# MCU_Power_Radio.net
KiCad netlist of a schematic drawn in Altium Designer
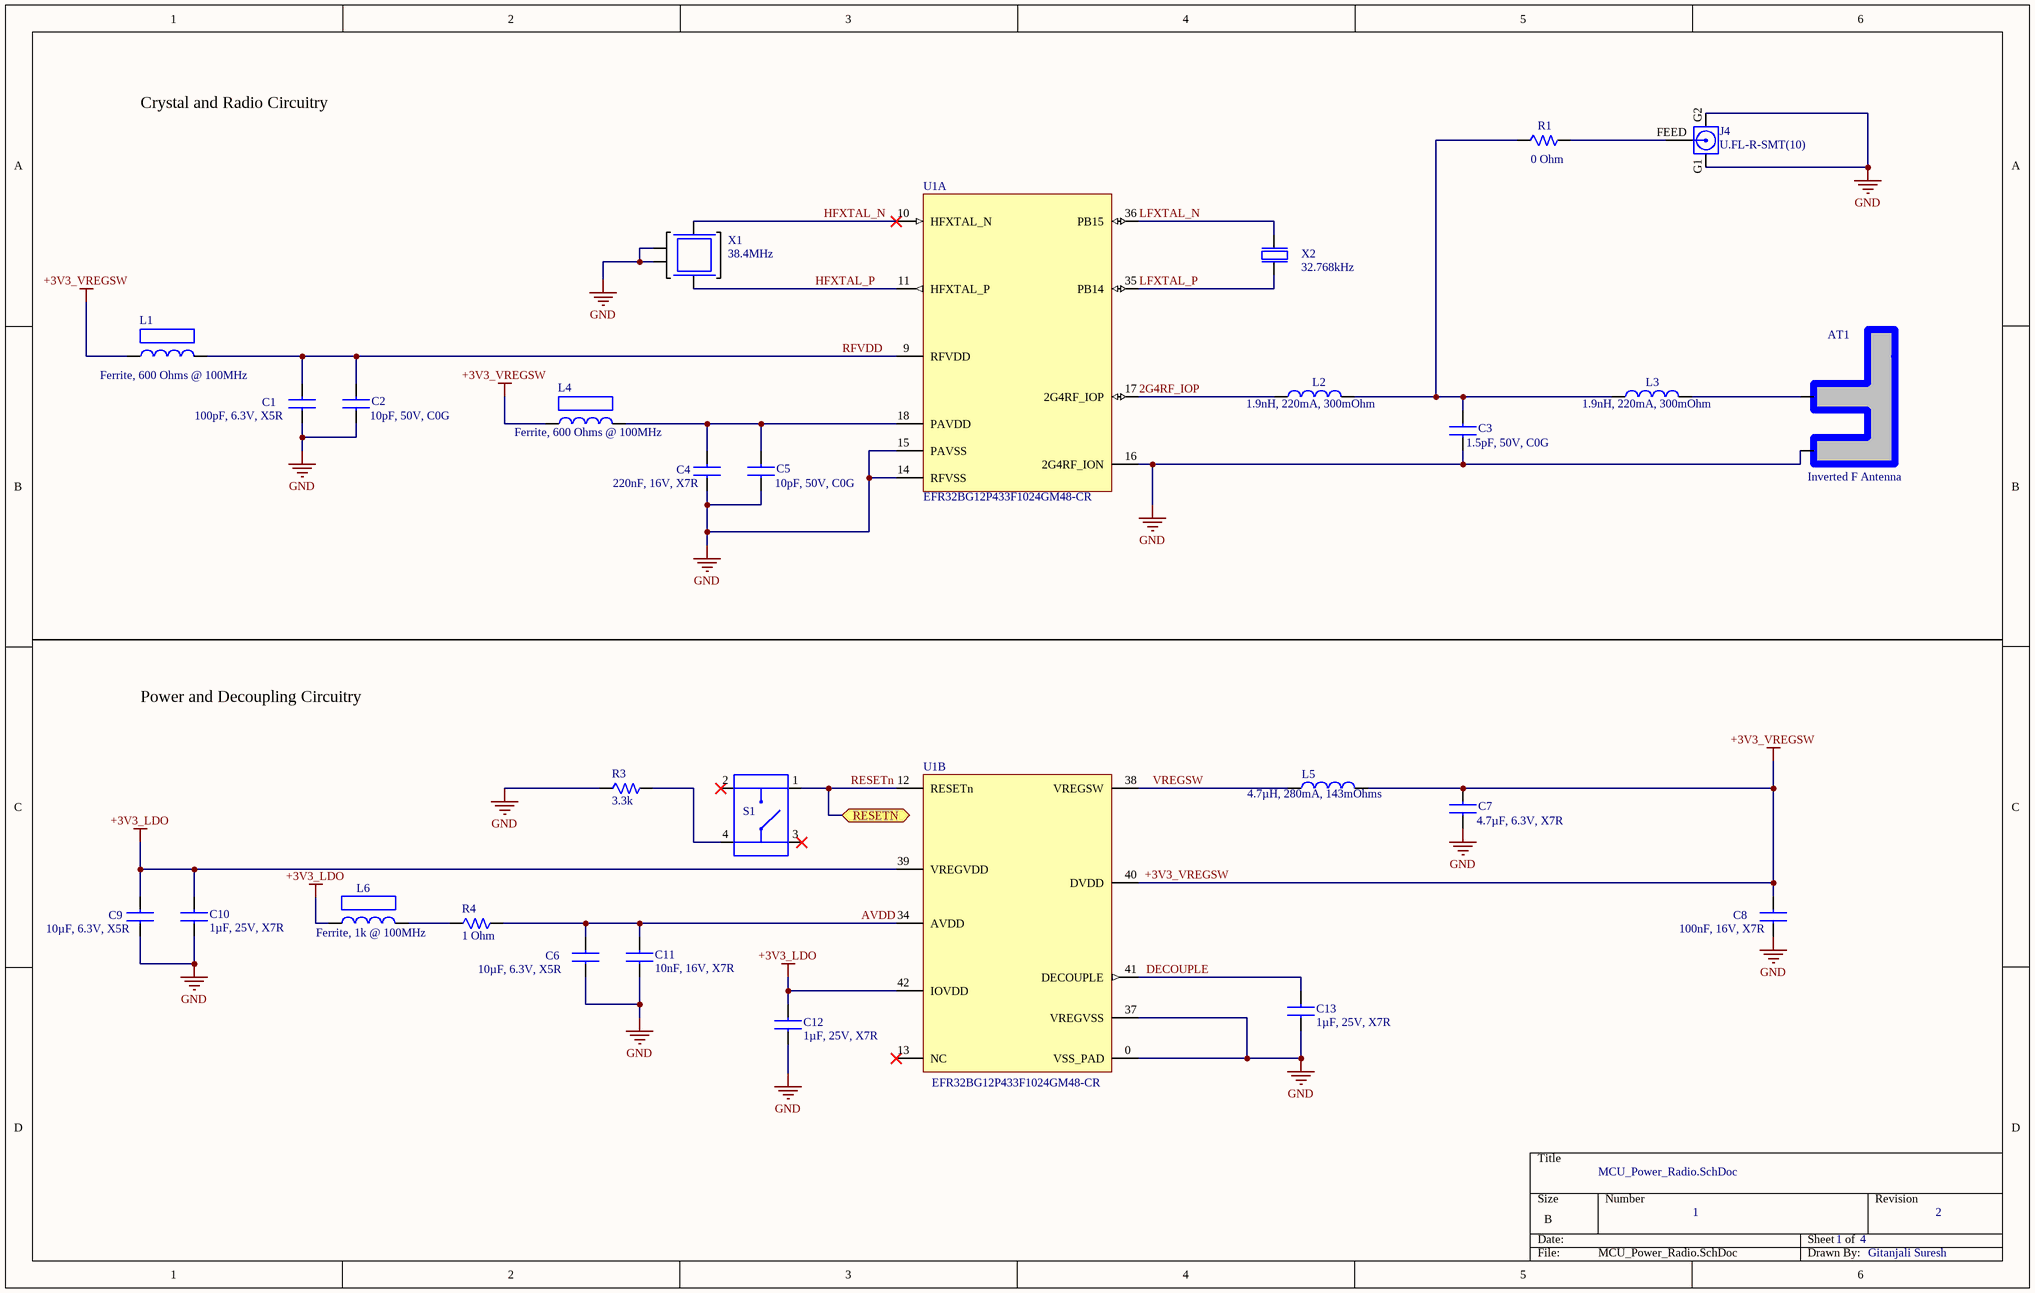
[diagram p0: MCU_Power_Radio.SchDoc]

(export (version "E")
  (design (tool "Eeschema 10.0.6"))
  (components
    (comp (ref "AT1")
      (value "Inverted F Antenna")
      (footprint "F-Antenna")
      (libsource (lib "PMIC_IR") (part "F_ANTENNA"))
    )
    (comp (ref "C1")
      (value "100pF, 6.3V, X5R")
      (footprint "CAP_X7R_100PF")
      (description "100 pF, 16 V, 0603 [1608 Metrické], ± 10%, X7R")
      (fields
        (field (name "MANUFACTURER") "Wurth Electronics")
        (field (name "MANUFACTURER PART NUMBER") "885012206028")
      )
      (libsource (lib "PMIC_IR") (part "885012206028"))
    )
    (comp (ref "C2")
      (value "10pF, 50V, C0G")
      (footprint "CAP_0805_10PF")
      (description "CERAMIC CAP 10PF 50V, C0G, 5%, 0805")
      (fields
        (field (name "MANUFACTURER") "Vishay")
        (field (name "MANUFACTURER PART NUMBER") "VJ0805A100JXACW1BC")
      )
      (libsource (lib "PMIC_IR") (part "VJ0805A100JXACW1BC"))
    )
    (comp (ref "C3")
      (value "1.5pF, 50V, C0G")
      (footprint "CAP_0402_1.5pF")
      (description "Cap Ceramic 1.5pF 50V C0G 0.05pF SMD 0402 125C Paper T/R")
      (fields
        (field (name "MANUFACTURER") "Murata")
        (field (name "MANUFACTURER PART NUMBER") "GJM1555C1H1R5WB01D")
      )
      (libsource (lib "PMIC_IR") (part "GJM1555C1H1R5WB01D"))
    )
    (comp (ref "C4")
      (value "220nF, 16V, X7R")
      (footprint "CAP_X7R_100PF")
      (fields
        (field (name "MANUFACTURER") "Yageo")
        (field (name "MANUFACTURER PART NUMBER") "CC0805KRX7R7BB224")
        (field (name "TOLERANCE") "10%")
      )
      (libsource (lib "PMIC_IR") (part "885012206048"))
    )
    (comp (ref "C5")
      (value "10pF, 50V, C0G")
      (footprint "CAP_0805_10PF")
      (description "CERAMIC CAP 10PF 50V, C0G, 5%, 0805")
      (fields
        (field (name "MANUFACTURER") "Vishay")
        (field (name "MANUFACTURER PART NUMBER") "VJ0805A100JXACW1BC")
      )
      (libsource (lib "PMIC_IR") (part "VJ0805A100JXACW1BC"))
    )
    (comp (ref "C6")
      (value "10µF, 6.3V, X5R")
      (footprint "CAP_X5R_10UF")
      (description "CAP CER 10UF 6.3V X5R 0805")
      (fields
        (field (name "MANUFACTURER") "Wurth Electronics")
        (field (name "MANUFACTURER PART NUMBER") "885012107004")
      )
      (libsource (lib "PMIC_IR") (part "885012107004"))
    )
    (comp (ref "C7")
      (value "4.7µF, 6.3V, X7R")
      (footprint "CAP_X7R_4.7uF")
      (description "4.7uF, 6.3 V, 0603 [1608 Metric], 10%, X7R, CL Series Ceramic Capacitor,")
      (fields
        (field (name "MANUFACTURER") "Samsung")
        (field (name "MANUFACTURER PART NUMBER") "CL10B475KQ8NQNC")
      )
      (libsource (lib "PMIC_IR") (part "CL10B475KQ8NQNC"))
    )
    (comp (ref "C8")
      (value "100nF, 16V, X7R")
      (footprint "CAP_X7R_100NF")
      (description "CAP 100NF 16V 0603")
      (fields
        (field (name "MANUFACTURER") "Murata")
        (field (name "MANUFACTURER PART NUMBER") "LLL215R71C104MA11L")
      )
      (libsource (lib "PMIC_IR") (part "C0603C104M4RACTU"))
    )
    (comp (ref "C9")
      (value "10µF, 6.3V, X5R")
      (footprint "CAP_X5R_10UF")
      (description "CAP CER 10UF 6.3V X5R 0805")
      (fields
        (field (name "MANUFACTURER") "Wurth Electronics")
        (field (name "MANUFACTURER PART NUMBER") "885012107004")
      )
      (libsource (lib "PMIC_IR") (part "885012107004"))
    )
    (comp (ref "C10")
      (value "1µF, 25V, X7R")
      (footprint "CAP_X7R_100PF")
      (description "CAP CER 1UF 25V X7R 0603")
      (fields
        (field (name "MANUFACTURER") "Yageo")
        (field (name "MANUFACTURER PART NUMBER") "CC1206MKX7R8BB105")
      )
      (libsource (lib "PMIC_IR") (part "885012206076"))
    )
    (comp (ref "C11")
      (value "10nF, 16V, X7R")
      (footprint "CAP_X7R_100PF")
      (description "CAP CER 10nF 16V X7R 0603")
      (fields
        (field (name "MANUFACTURER") "Yageo")
        (field (name "MANUFACTURER PART NUMBER") "CC0402MRX7R7BB103")
      )
      (libsource (lib "PMIC_IR") (part "885012206040"))
    )
    (comp (ref "C12")
      (value "1µF, 25V, X7R")
      (footprint "CAP_X7R_100PF")
      (description "CAP CER 1UF 25V X7R 0603")
      (fields
        (field (name "MANUFACTURER") "Yageo")
        (field (name "MANUFACTURER PART NUMBER") "CC1206MKX7R8BB105")
      )
      (libsource (lib "PMIC_IR") (part "885012206076"))
    )
    (comp (ref "C13")
      (value "1µF, 25V, X7R")
      (footprint "CAP_X7R_100PF")
      (description "CAP CER 1UF 25V X7R 0603")
      (fields
        (field (name "MANUFACTURER") "Yageo")
        (field (name "MANUFACTURER PART NUMBER") "CC1206MKX7R8BB105")
      )
      (libsource (lib "PMIC_IR") (part "885012206076"))
    )
    (comp (ref "J4")
      (value "U.FL-R-SMT(10)")
      (footprint "U.FL_connector")
      (description "CONN UMC JACK STR 50 OHM SMD")
      (fields (field (name "MANUFACTURER") "Hirose Electric Co Ltd"))
      (libsource (lib "PMIC_IR") (part "U.FL connector U.FL-R-SMT(10)"))
    )
    (comp (ref "L1")
      (value "Ferrite, 600 Ohms @ 100MHz")
      (footprint "Ferrite_Bead_0603")
      (description "BLM18AG601SN1D - Ferrite Bead, 0603 / 1608, 600 ohm, 500 mA, Série BLM18A, 0.38 ohm, ± 25%")
      (fields
        (field (name "MANUFACTURER") "Murata")
        (field (name "MANUFACTURER PART NUMBER") "BLM18AG601SN1D")
      )
      (libsource (lib "PMIC_IR") (part "BLM18AG601SN1D"))
    )
    (comp (ref "L2")
      (value "1.9nH, 220mA, 300mOhm")
      (footprint "INDC1005X04N_1.9NH")
      (description "Inductor 1.9nH 500MHz 13Q-Factor 220mA 300mOhm DCR 0402 Paper T/R")
      (fields
        (field (name "MANUFACTURER") "Murata")
        (field (name "MANUFACTURER PART NUMBER") "LQP15MN1N9W02D")
      )
      (libsource (lib "PMIC_IR") (part "LQP15MN1N9W02D"))
    )
    (comp (ref "L3")
      (value "1.9nH, 220mA, 300mOhm")
      (footprint "INDC1005X04N_1.9NH")
      (description "Inductor 1.9nH 500MHz 13Q-Factor 220mA 300mOhm DCR 0402 Paper T/R")
      (fields
        (field (name "MANUFACTURER") "Murata")
        (field (name "MANUFACTURER PART NUMBER") "LQP15MN1N9W02D")
      )
      (libsource (lib "PMIC_IR") (part "LQP15MN1N9W02D"))
    )
    (comp (ref "L4")
      (value "Ferrite, 600 Ohms @ 100MHz")
      (footprint "Ferrite_Bead_0603")
      (description "BLM18AG601SN1D - Ferrite Bead, 0603 / 1608, 600 ohm, 500 mA, Série BLM18A, 0.38 ohm, ± 25%")
      (fields
        (field (name "MANUFACTURER") "Murata")
        (field (name "MANUFACTURER PART NUMBER") "BLM18AG601SN1D")
      )
      (libsource (lib "PMIC_IR") (part "BLM18AG601SN1D"))
    )
    (comp (ref "L5")
      (value "4.7µH, 280mA, 143mOhms")
      (footprint "IND_2228x1")
      (fields
        (field (name "MANUFACTURER") "Wurth Electronics")
        (field (name "MANUFACTURER PART NUMBER") "74479787247")
      )
      (libsource (lib "PMIC_IR") (part "74479787247"))
    )
    (comp (ref "L6")
      (value "Ferrite, 1k @ 100MHz")
      (footprint "Ferrite_Bead_1801x1")
      (description "Ferrite Bead, 0603 [1608 Metric], 1 kohm, 200 mA, WE-CBF Series, 0.6 ohm, ± 25%")
      (fields
        (field (name "MANUFACTURER") "Wurth Electronics")
        (field (name "MANUFACTURER PART NUMBER") "74279266")
      )
      (libsource (lib "PMIC_IR") (part "74279266"))
    )
    (comp (ref "R1")
      (value "0 Ohm")
      (footprint "RES_0_0603")
      (description "Jumper, 0 ohm, 0603 [Metrisch 1608], Baureihe RC, 75 V, Dickschicht")
      (fields
        (field (name "MANUFACTURER") "Yageo")
        (field (name "MANUFACTURER PART NUMBER") "RC0603JR-070RL")
      )
      (libsource (lib "PMIC_IR") (part "RC0603JR-070RL"))
    )
    (comp (ref "R3")
      (value "3.3k")
      (footprint "RES_0603_3.3k")
      (description "RES SMD 3.3 KOHM 1% 0.3W 0603")
      (fields
        (field (name "MANUFACTURER") "Yageo")
        (field (name "MANUFACTURER PART NUMBER") "RC0201FR-07100RL")
      )
      (libsource (lib "PMIC_IR") (part "SDR03EZPF3301"))
    )
    (comp (ref "R4")
      (value "1 Ohm")
      (footprint "RES_0603_10k")
      (description "RES SMD 1 OHM 1% 1/10W 0603")
      (fields
        (field (name "MANUFACTURER") "Vishay")
        (field (name "MANUFACTURER PART NUMBER") "CRCW04021R00FNED")
      )
      (libsource (lib "PMIC_IR") (part "KTR03EZPF1R00"))
    )
    (comp (ref "S1")
      (value "TACTILE SWITCH")
      (footprint "SW_PTS645SK50SMTR92LFS")
      (description "TACTILE SWITCH, SPST, 0.05A, 12VDC")
      (fields
        (field (name "MANUFACTURER") "ITT C&K")
        (field (name "MANUFACTURER PART NUMBER") "PTS645SL50SMTR92LFS")
      )
      (libsource (lib "PMIC_IR") (part "PTS645SL50SMTR92LFS"))
    )
    (comp (ref "U1")
      (value "EFR32BG12P433F1024GM48-CR")
      (footprint "QFN50P700X700X90_HS-49N")
      (description "Blue Gecko EFR32BG13")
      (fields (field (name "MANUFACTURER") "Silicon Labs"))
      (libsource (lib "PMIC_IR") (part "EFR32BG12P433F1024GM48-CR"))
    )
    (comp (ref "X1")
      (value "38.4MHz")
      (footprint "OSCSC220P320X250X70-4N")
      (description "±10ppm Crystal 10pF 4-SMD, No Lead")
      (fields
        (field (name "MANUFACTURER") "Jauch")
        (field (name "MANUFACTURER PART NUMBER") "Q 38,40-JXS21-10-10/15-T1-FU-WA-LF")
      )
      (libsource (lib "PMIC_IR") (part "Q 38,40-JXS21-10-10/15-T1-FU-WA-LF"))
    )
    (comp (ref "X2")
      (value "32.768kHz")
      (footprint "XTAL320X150X90")
      (description "Crystals 32.768kHz AECQ200 12.5pF -40C +85C")
      (fields
        (field (name "MANUFACTURER") "Abracon")
        (field (name "MANUFACTURER PART NUMBER") "ABS07AIG-32.768KHZ-D-T")
      )
      (libsource (lib "PMIC_IR") (part "ABS07AIG-32.768KHZ-D-T"))
    )
  )
  (nets
    (net (code "1") (name "+3V3_LDO") (class "Default")
      (node (ref "C10") (pin "2") (pinfunction "2_2") (pintype "passive"))
      (node (ref "C12") (pin "2") (pinfunction "2_2") (pintype "passive"))
      (node (ref "C9") (pin "1") (pinfunction "1_1") (pintype "passive"))
      (node (ref "L6") (pin "2") (pinfunction "2_2") (pintype "passive"))
      (node (ref "U1") (pin "39") (pinfunction "VREGVDD_39") (pintype "power_in"))
      (node (ref "U1") (pin "42") (pinfunction "IOVDD_42") (pintype "power_in"))
    )
    (net (code "2") (name "+3V3_VREGSW") (class "Default")
      (node (ref "C7") (pin "1") (pinfunction "1_1") (pintype "passive"))
      (node (ref "C8") (pin "2") (pinfunction "2_2") (pintype "passive"))
      (node (ref "L1") (pin "1") (pinfunction "1_1") (pintype "passive"))
      (node (ref "L4") (pin "1") (pinfunction "1_1") (pintype "passive"))
      (node (ref "L5") (pin "2") (pinfunction "2_2") (pintype "passive"))
      (node (ref "U1") (pin "40") (pinfunction "DVDD_40") (pintype "power_in"))
    )
    (net (code "3") (name "/2G4RF_IOP") (class "Default")
      (node (ref "L2") (pin "1") (pinfunction "1_1") (pintype "passive"))
      (node (ref "U1") (pin "17") (pinfunction "2G4RF_IOP_17") (pintype "bidirectional"))
    )
    (net (code "4") (name "/AVDD") (class "Default")
      (node (ref "C11") (pin "2") (pinfunction "2_2") (pintype "passive"))
      (node (ref "C6") (pin "2") (pinfunction "2_2") (pintype "passive"))
      (node (ref "R4") (pin "2") (pinfunction "2_2") (pintype "passive"))
      (node (ref "U1") (pin "34") (pinfunction "AVDD_34") (pintype "power_in"))
    )
    (net (code "5") (name "/DECOUPLE") (class "Default")
      (node (ref "C13") (pin "2") (pinfunction "2_2") (pintype "passive"))
      (node (ref "U1") (pin "41") (pinfunction "DECOUPLE_41") (pintype "output"))
    )
    (net (code "6") (name "/HFXTAL_N") (class "Default")
      (node (ref "U1") (pin "10") (pinfunction "HFXTAL_N_10") (pintype "input"))
      (node (ref "X1") (pin "3") (pinfunction "3_3") (pintype "passive"))
    )
    (net (code "7") (name "/HFXTAL_P") (class "Default")
      (node (ref "U1") (pin "11") (pinfunction "HFXTAL_P_11") (pintype "output"))
      (node (ref "X1") (pin "1") (pinfunction "1_1") (pintype "passive"))
    )
    (net (code "8") (name "/LFXTAL_N") (class "Default")
      (node (ref "U1") (pin "36") (pinfunction "PB15_36") (pintype "bidirectional"))
      (node (ref "X2") (pin "1") (pinfunction "1_1") (pintype "passive"))
    )
    (net (code "9") (name "/LFXTAL_P") (class "Default")
      (node (ref "U1") (pin "35") (pinfunction "PB14_35") (pintype "bidirectional"))
      (node (ref "X2") (pin "2") (pinfunction "2_2") (pintype "passive"))
    )
    (net (code "10") (name "/RESETn") (class "Default")
      (node (ref "S1") (pin "1") (pinfunction "1_1") (pintype "passive"))
      (node (ref "U1") (pin "12") (pinfunction "RESETn_12") (pintype "passive"))
    )
    (net (code "11") (name "/RFVDD") (class "Default")
      (node (ref "C1") (pin "2") (pinfunction "2_2") (pintype "passive"))
      (node (ref "C2") (pin "1") (pinfunction "1_1") (pintype "passive"))
      (node (ref "L1") (pin "2") (pinfunction "2_2") (pintype "passive"))
      (node (ref "U1") (pin "9") (pinfunction "RFVDD_9") (pintype "power_in"))
    )
    (net (code "12") (name "/VREGSW") (class "Default")
      (node (ref "L5") (pin "1") (pinfunction "1_1") (pintype "passive"))
      (node (ref "U1") (pin "38") (pinfunction "VREGSW_38") (pintype "power_in"))
    )
    (net (code "13") (name "GND") (class "Default")
      (node (ref "AT1") (pin "1") (pinfunction "GND_1") (pintype "passive"))
      (node (ref "C1") (pin "1") (pinfunction "1_1") (pintype "passive"))
      (node (ref "C10") (pin "1") (pinfunction "1_1") (pintype "passive"))
      (node (ref "C11") (pin "1") (pinfunction "1_1") (pintype "passive"))
      (node (ref "C12") (pin "1") (pinfunction "1_1") (pintype "passive"))
      (node (ref "C13") (pin "1") (pinfunction "1_1") (pintype "passive"))
      (node (ref "C2") (pin "2") (pinfunction "2_2") (pintype "passive"))
      (node (ref "C3") (pin "2") (pinfunction "2_2") (pintype "passive"))
      (node (ref "C4") (pin "1") (pinfunction "1_1") (pintype "passive"))
      (node (ref "C5") (pin "2") (pinfunction "2_2") (pintype "passive"))
      (node (ref "C6") (pin "1") (pinfunction "1_1") (pintype "passive"))
      (node (ref "C7") (pin "2") (pinfunction "2_2") (pintype "passive"))
      (node (ref "C8") (pin "1") (pinfunction "1_1") (pintype "passive"))
      (node (ref "C9") (pin "2") (pinfunction "2_2") (pintype "passive"))
      (node (ref "J4") (pin "G1") (pinfunction "GND1_G1") (pintype "power_in"))
      (node (ref "J4") (pin "G2") (pinfunction "GND2_G2") (pintype "power_in"))
      (node (ref "R3") (pin "1") (pinfunction "1_1") (pintype "passive"))
      (node (ref "U1") (pin "0") (pinfunction "VSS_PAD_0") (pintype "power_in"))
      (node (ref "U1") (pin "14") (pinfunction "RFVSS_14") (pintype "power_in"))
      (node (ref "U1") (pin "15") (pinfunction "PAVSS_15") (pintype "power_in"))
      (node (ref "U1") (pin "16") (pinfunction "2G4RF_ION_16") (pintype "passive"))
      (node (ref "U1") (pin "37") (pinfunction "VREGVSS_37") (pintype "power_in"))
      (node (ref "X1") (pin "2") (pinfunction "2_2") (pintype "passive"))
      (node (ref "X1") (pin "4") (pinfunction "4_4") (pintype "passive"))
    )
    (net (code "14") (name "Net-(AT1-FEED)") (class "Default")
      (node (ref "AT1") (pin "2") (pinfunction "FEED_2") (pintype "passive"))
      (node (ref "L3") (pin "2") (pinfunction "2_2") (pintype "passive"))
    )
    (net (code "15") (name "Net-(C3-Pad1)") (class "Default")
      (node (ref "C3") (pin "1") (pinfunction "1_1") (pintype "passive"))
      (node (ref "L2") (pin "2") (pinfunction "2_2") (pintype "passive"))
      (node (ref "L3") (pin "1") (pinfunction "1_1") (pintype "passive"))
      (node (ref "R1") (pin "1") (pinfunction "1_1") (pintype "passive"))
    )
    (net (code "16") (name "Net-(J4-PadFEED)") (class "Default")
      (node (ref "J4") (pin "FEED") (pinfunction "FEED_FEED") (pintype "passive"))
      (node (ref "R1") (pin "2") (pinfunction "2_2") (pintype "passive"))
    )
    (net (code "17") (name "Net-(L6-Pad1)") (class "Default")
      (node (ref "L6") (pin "1") (pinfunction "1_1") (pintype "passive"))
      (node (ref "R4") (pin "1") (pinfunction "1_1") (pintype "passive"))
    )
    (net (code "18") (name "Net-(R3-Pad2)") (class "Default")
      (node (ref "R3") (pin "2") (pinfunction "2_2") (pintype "passive"))
      (node (ref "S1") (pin "4") (pinfunction "4_4") (pintype "passive"))
    )
    (net (code "19") (name "Net-(U1A-PAVDD)") (class "Default")
      (node (ref "C4") (pin "2") (pinfunction "2_2") (pintype "passive"))
      (node (ref "C5") (pin "1") (pinfunction "1_1") (pintype "passive"))
      (node (ref "L4") (pin "2") (pinfunction "2_2") (pintype "passive"))
      (node (ref "U1") (pin "18") (pinfunction "PAVDD_18") (pintype "power_in"))
    )
    (net (code "20") (name "unconnected-(S1-Pad2)") (class "Default")
      (node (ref "S1") (pin "2") (pinfunction "2_2") (pintype "passive+no_connect"))
    )
    (net (code "21") (name "unconnected-(S1-Pad3)") (class "Default")
      (node (ref "S1") (pin "3") (pinfunction "3_3") (pintype "passive+no_connect"))
    )
    (net (code "22") (name "unconnected-(U1B-NC-Pad13)") (class "Default")
      (node (ref "U1") (pin "13") (pinfunction "NC_13") (pintype "power_in+no_connect"))
    )
  )
)
